# velodyne.net
KiCad netlist of a schematic drawn in EAGLE
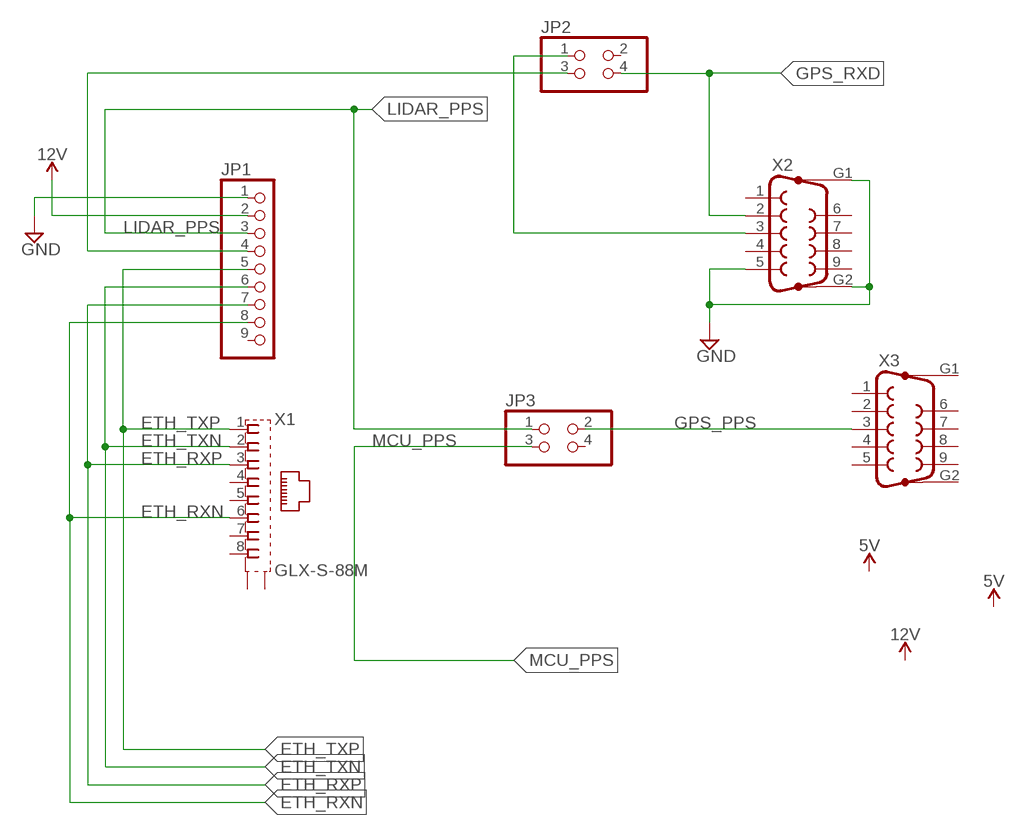
[diagram p0: schematic, sheet 1]

(export (version "E")
  (design (tool "Eeschema 10.0.6"))
  (components
    (comp (ref "JP1")
      (value "PINHD-1X9")
      (footprint "eagle-import:1X09")
      (libsource (lib "eagle-import") (part "PINHD-1X9"))
    )
    (comp (ref "JP2")
      (value "PINHD-2X2")
      (footprint "eagle-import:2X02")
      (libsource (lib "eagle-import") (part "PINHD-2X2"))
    )
    (comp (ref "JP3")
      (value "PINHD-2X2")
      (footprint "eagle-import:2X02")
      (libsource (lib "eagle-import") (part "PINHD-2X2"))
    )
    (comp (ref "X1")
      (value "GLX-S-88M")
      (footprint "eagle-import:GLX-S-88M")
      (libsource (lib "eagle-import") (part "GLX-S-88M"))
    )
    (comp (ref "X2")
      (value "F09VP")
      (footprint "eagle-import:F09VP")
      (libsource (lib "eagle-import") (part "F09VP"))
    )
    (comp (ref "X3")
      (value "F09VP")
      (footprint "eagle-import:F09VP")
      (libsource (lib "eagle-import") (part "F09VP"))
    )
  )
  (nets
    (net (code "1") (name "/GPS_PPS") (class "Default")
      (node (ref "JP3") (pin "2") (pinfunction "2_2") (pintype "passive"))
      (node (ref "X3") (pin "3") (pinfunction "3_3") (pintype "passive"))
    )
    (net (code "3") (name "12V") (class "Default")
      (node (ref "JP1") (pin "2") (pinfunction "2_2") (pintype "passive"))
    )
    (net (code "4") (name "ETH_RXN") (class "Default")
      (node (ref "JP1") (pin "8") (pinfunction "8_8") (pintype "passive"))
      (node (ref "X1") (pin "6") (pinfunction "6_6") (pintype "passive"))
    )
    (net (code "5") (name "ETH_RXP") (class "Default")
      (node (ref "JP1") (pin "7") (pinfunction "7_7") (pintype "passive"))
      (node (ref "X1") (pin "3") (pinfunction "3_3") (pintype "passive"))
    )
    (net (code "6") (name "ETH_TXN") (class "Default")
      (node (ref "JP1") (pin "6") (pinfunction "6_6") (pintype "passive"))
      (node (ref "X1") (pin "2") (pinfunction "2_2") (pintype "passive"))
    )
    (net (code "7") (name "ETH_TXP") (class "Default")
      (node (ref "JP1") (pin "5") (pinfunction "5_5") (pintype "passive"))
      (node (ref "X1") (pin "1") (pinfunction "1_1") (pintype "passive"))
    )
    (net (code "8") (name "GND") (class "Default")
      (node (ref "JP1") (pin "1") (pinfunction "1_1") (pintype "passive"))
      (node (ref "X2") (pin "5") (pinfunction "5_5") (pintype "passive"))
      (node (ref "X2") (pin "G1") (pinfunction "G1_G1") (pintype "passive"))
      (node (ref "X2") (pin "G2") (pinfunction "G2_G2") (pintype "passive"))
    )
    (net (code "9") (name "GPS_RXD") (class "Default")
      (node (ref "JP2") (pin "4") (pinfunction "4_4") (pintype "passive"))
      (node (ref "X2") (pin "2") (pinfunction "2_2") (pintype "passive"))
    )
    (net (code "10") (name "LIDAR_PPS") (class "Default")
      (node (ref "JP1") (pin "3") (pinfunction "3_3") (pintype "passive"))
      (node (ref "JP3") (pin "1") (pinfunction "1_1") (pintype "passive"))
    )
    (net (code "11") (name "MCU_PPS") (class "Default")
      (node (ref "JP3") (pin "3") (pinfunction "3_3") (pintype "passive"))
    )
    (net (code "12") (name "Net-(JP1-Pad4)") (class "Default")
      (node (ref "JP1") (pin "4") (pinfunction "4_4") (pintype "passive"))
      (node (ref "JP2") (pin "3") (pinfunction "3_3") (pintype "passive"))
    )
    (net (code "13") (name "Net-(JP2-Pad1)") (class "Default")
      (node (ref "JP2") (pin "1") (pinfunction "1_1") (pintype "passive"))
      (node (ref "X2") (pin "3") (pinfunction "3_3") (pintype "passive"))
    )
    (net (code "14") (name "unconnected-(JP1-Pad9)") (class "Default")
      (node (ref "JP1") (pin "9") (pinfunction "9_9") (pintype "passive"))
    )
    (net (code "15") (name "unconnected-(JP2-Pad2)") (class "Default")
      (node (ref "JP2") (pin "2") (pinfunction "2_2") (pintype "passive"))
    )
    (net (code "16") (name "unconnected-(JP3-Pad4)") (class "Default")
      (node (ref "JP3") (pin "4") (pinfunction "4_4") (pintype "passive"))
    )
    (net (code "17") (name "unconnected-(X1-Pad4)") (class "Default")
      (node (ref "X1") (pin "4") (pinfunction "4_4") (pintype "passive"))
    )
    (net (code "18") (name "unconnected-(X1-Pad5)") (class "Default")
      (node (ref "X1") (pin "5") (pinfunction "5_5") (pintype "passive"))
    )
    (net (code "19") (name "unconnected-(X1-Pad7)") (class "Default")
      (node (ref "X1") (pin "7") (pinfunction "7_7") (pintype "passive"))
    )
    (net (code "20") (name "unconnected-(X1-Pad8)") (class "Default")
      (node (ref "X1") (pin "8") (pinfunction "8_8") (pintype "passive"))
    )
    (net (code "21") (name "unconnected-(X1-PadS1)") (class "Default")
      (node (ref "X1") (pin "S1") (pinfunction "S1_S1") (pintype "passive"))
    )
    (net (code "22") (name "unconnected-(X1-PadS2)") (class "Default")
      (node (ref "X1") (pin "S2") (pinfunction "S2_S2") (pintype "passive"))
    )
    (net (code "23") (name "unconnected-(X2-Pad1)") (class "Default")
      (node (ref "X2") (pin "1") (pinfunction "1_1") (pintype "passive"))
    )
    (net (code "24") (name "unconnected-(X2-Pad4)") (class "Default")
      (node (ref "X2") (pin "4") (pinfunction "4_4") (pintype "passive"))
    )
    (net (code "25") (name "unconnected-(X2-Pad6)") (class "Default")
      (node (ref "X2") (pin "6") (pinfunction "6_6") (pintype "passive"))
    )
    (net (code "26") (name "unconnected-(X2-Pad7)") (class "Default")
      (node (ref "X2") (pin "7") (pinfunction "7_7") (pintype "passive"))
    )
    (net (code "27") (name "unconnected-(X2-Pad8)") (class "Default")
      (node (ref "X2") (pin "8") (pinfunction "8_8") (pintype "passive"))
    )
    (net (code "28") (name "unconnected-(X2-Pad9)") (class "Default")
      (node (ref "X2") (pin "9") (pinfunction "9_9") (pintype "passive"))
    )
    (net (code "29") (name "unconnected-(X3-Pad1)") (class "Default")
      (node (ref "X3") (pin "1") (pinfunction "1_1") (pintype "passive"))
    )
    (net (code "30") (name "unconnected-(X3-Pad2)") (class "Default")
      (node (ref "X3") (pin "2") (pinfunction "2_2") (pintype "passive"))
    )
    (net (code "31") (name "unconnected-(X3-Pad4)") (class "Default")
      (node (ref "X3") (pin "4") (pinfunction "4_4") (pintype "passive"))
    )
    (net (code "32") (name "unconnected-(X3-Pad5)") (class "Default")
      (node (ref "X3") (pin "5") (pinfunction "5_5") (pintype "passive"))
    )
    (net (code "33") (name "unconnected-(X3-Pad6)") (class "Default")
      (node (ref "X3") (pin "6") (pinfunction "6_6") (pintype "passive"))
    )
    (net (code "34") (name "unconnected-(X3-Pad7)") (class "Default")
      (node (ref "X3") (pin "7") (pinfunction "7_7") (pintype "passive"))
    )
    (net (code "35") (name "unconnected-(X3-Pad8)") (class "Default")
      (node (ref "X3") (pin "8") (pinfunction "8_8") (pintype "passive"))
    )
    (net (code "36") (name "unconnected-(X3-Pad9)") (class "Default")
      (node (ref "X3") (pin "9") (pinfunction "9_9") (pintype "passive"))
    )
    (net (code "37") (name "unconnected-(X3-PadG1)") (class "Default")
      (node (ref "X3") (pin "G1") (pinfunction "G1_G1") (pintype "passive"))
    )
    (net (code "38") (name "unconnected-(X3-PadG2)") (class "Default")
      (node (ref "X3") (pin "G2") (pinfunction "G2_G2") (pintype "passive"))
    )
  )
)
